# NusbioV2_Board.net
KiCad netlist of a schematic drawn in EAGLE
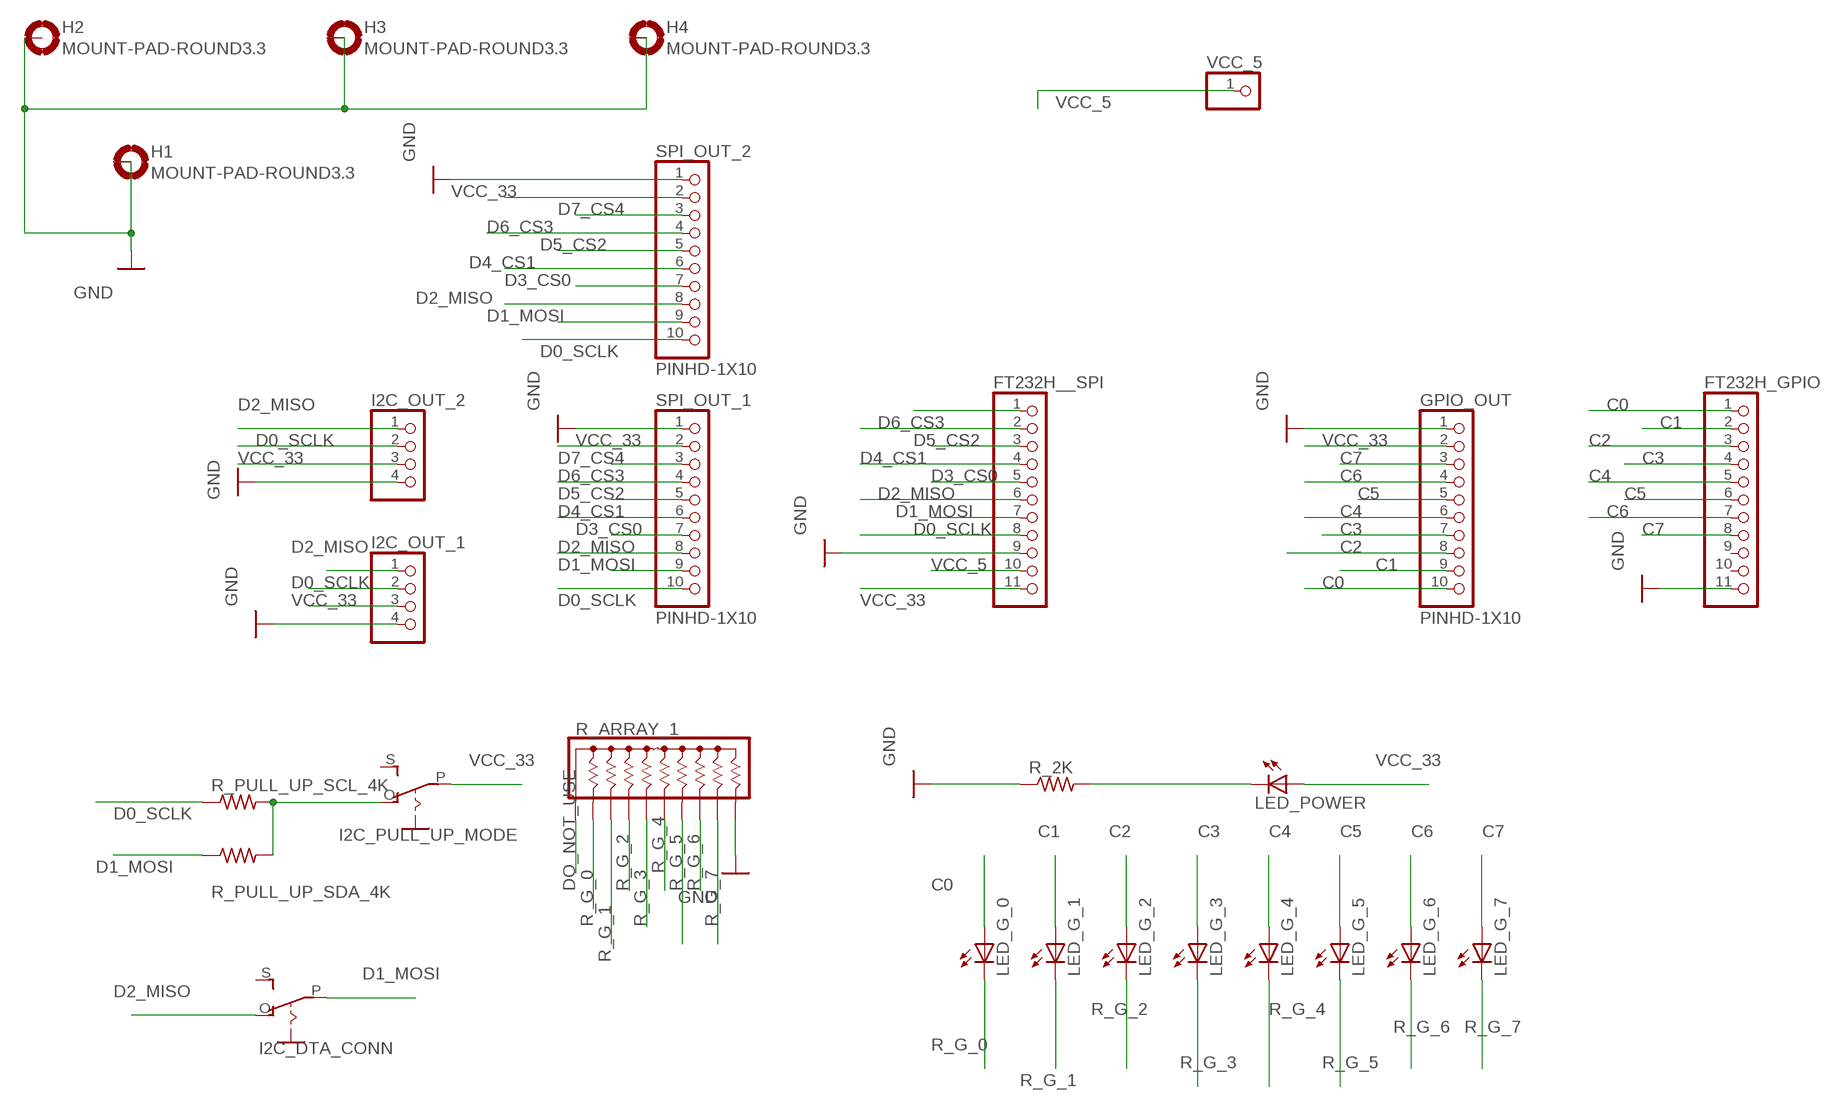
[diagram p0: schematic, sheet 1]

(export (version "E")
  (design (tool "Eeschema 10.0.6"))
  (components
    (comp (ref "FT232H_GPIO")
      (value "PINHD-1X11")
      (footprint "eagle-import:1X11")
      (libsource (lib "eagle-import") (part "PINHD-1X11"))
    )
    (comp (ref "FT232H__SPI")
      (value "PINHD-1X11")
      (footprint "eagle-import:1X11")
      (libsource (lib "eagle-import") (part "PINHD-1X11"))
    )
    (comp (ref "GPIO_OUT")
      (value "PINHD-1X10")
      (footprint "eagle-import:1X10-BIG")
      (libsource (lib "eagle-import") (part "PINHD-1X10"))
    )
    (comp (ref "H1")
      (value "MOUNT-PAD-ROUND3.3")
      (footprint "eagle-import:3,3-PAD")
      (libsource (lib "eagle-import") (part "MOUNT-PAD-ROUND3.3"))
    )
    (comp (ref "H2")
      (value "MOUNT-PAD-ROUND3.3")
      (footprint "eagle-import:3,3-PAD")
      (libsource (lib "eagle-import") (part "MOUNT-PAD-ROUND3.3"))
    )
    (comp (ref "H3")
      (value "MOUNT-PAD-ROUND3.3")
      (footprint "eagle-import:3,3-PAD")
      (libsource (lib "eagle-import") (part "MOUNT-PAD-ROUND3.3"))
    )
    (comp (ref "H4")
      (value "MOUNT-PAD-ROUND3.3")
      (footprint "eagle-import:3,3-PAD")
      (libsource (lib "eagle-import") (part "MOUNT-PAD-ROUND3.3"))
    )
    (comp (ref "I2C_DTA_CONN")
      (value "EG1218S")
      (footprint "eagle-import:EG1218")
      (libsource (lib "eagle-import") (part "EG1218S"))
    )
    (comp (ref "I2C_OUT_1")
      (value "PINHD-1X4")
      (footprint "eagle-import:1X04")
      (libsource (lib "eagle-import") (part "PINHD-1X4"))
    )
    (comp (ref "I2C_OUT_2")
      (value "PINHD-1X4")
      (footprint "eagle-import:1X04")
      (libsource (lib "eagle-import") (part "PINHD-1X4"))
    )
    (comp (ref "I2C_PULL_UP_MODE")
      (value "EG1218S")
      (footprint "eagle-import:EG1218")
      (libsource (lib "eagle-import") (part "EG1218S"))
    )
    (comp (ref "LED_G_0")
      (value "LEDSMT1206")
      (footprint "eagle-import:1206")
      (libsource (lib "eagle-import") (part "LEDSMT1206"))
    )
    (comp (ref "LED_G_1")
      (value "LEDSMT1206")
      (footprint "eagle-import:1206")
      (libsource (lib "eagle-import") (part "LEDSMT1206"))
    )
    (comp (ref "LED_G_2")
      (value "LEDSMT1206")
      (footprint "eagle-import:1206")
      (libsource (lib "eagle-import") (part "LEDSMT1206"))
    )
    (comp (ref "LED_G_3")
      (value "LEDSMT1206")
      (footprint "eagle-import:1206")
      (libsource (lib "eagle-import") (part "LEDSMT1206"))
    )
    (comp (ref "LED_G_4")
      (value "LEDSMT1206")
      (footprint "eagle-import:1206")
      (libsource (lib "eagle-import") (part "LEDSMT1206"))
    )
    (comp (ref "LED_G_5")
      (value "LEDSMT1206")
      (footprint "eagle-import:1206")
      (libsource (lib "eagle-import") (part "LEDSMT1206"))
    )
    (comp (ref "LED_G_6")
      (value "LEDSMT1206")
      (footprint "eagle-import:1206")
      (libsource (lib "eagle-import") (part "LEDSMT1206"))
    )
    (comp (ref "LED_G_7")
      (value "LEDSMT1206")
      (footprint "eagle-import:1206")
      (libsource (lib "eagle-import") (part "LEDSMT1206"))
    )
    (comp (ref "LED_POWER")
      (value "LEDSMT1206")
      (footprint "eagle-import:1206")
      (libsource (lib "eagle-import") (part "LEDSMT1206"))
    )
    (comp (ref "R_2K")
      (value "R-US_R1206")
      (footprint "eagle-import:R1206")
      (libsource (lib "eagle-import") (part "R-US_R1206"))
    )
    (comp (ref "R_ARRAY_1")
      (value "4610X")
      (footprint "eagle-import:SIP10")
      (libsource (lib "eagle-import") (part "4610X"))
    )
    (comp (ref "R_PULL_UP_SCL_4K")
      (value "R-US_R1206")
      (footprint "eagle-import:R1206")
      (libsource (lib "eagle-import") (part "R-US_R1206"))
    )
    (comp (ref "R_PULL_UP_SDA_4K")
      (value "R-US_R1206")
      (footprint "eagle-import:R1206")
      (libsource (lib "eagle-import") (part "R-US_R1206"))
    )
    (comp (ref "SPI_OUT_1")
      (value "PINHD-1X10")
      (footprint "eagle-import:1X10-BIG")
      (libsource (lib "eagle-import") (part "PINHD-1X10"))
    )
    (comp (ref "SPI_OUT_2")
      (value "PINHD-1X10")
      (footprint "eagle-import:1X10-BIG")
      (libsource (lib "eagle-import") (part "PINHD-1X10"))
    )
    (comp (ref "VCC_5")
      (value "PINHD-1X1")
      (footprint "eagle-import:1X01")
      (libsource (lib "eagle-import") (part "PINHD-1X1"))
    )
  )
  (nets
    (net (code "1") (name "/C0") (class "Default")
      (node (ref "FT232H_GPIO") (pin "1") (pinfunction "1_1") (pintype "passive"))
      (node (ref "GPIO_OUT") (pin "10") (pinfunction "10_10") (pintype "passive"))
      (node (ref "LED_G_0") (pin "A") (pinfunction "A_A") (pintype "passive"))
    )
    (net (code "2") (name "/C1") (class "Default")
      (node (ref "FT232H_GPIO") (pin "2") (pinfunction "2_2") (pintype "passive"))
      (node (ref "GPIO_OUT") (pin "9") (pinfunction "9_9") (pintype "passive"))
      (node (ref "LED_G_1") (pin "A") (pinfunction "A_A") (pintype "passive"))
    )
    (net (code "3") (name "/C2") (class "Default")
      (node (ref "FT232H_GPIO") (pin "3") (pinfunction "3_3") (pintype "passive"))
      (node (ref "GPIO_OUT") (pin "8") (pinfunction "8_8") (pintype "passive"))
      (node (ref "LED_G_2") (pin "A") (pinfunction "A_A") (pintype "passive"))
    )
    (net (code "4") (name "/C3") (class "Default")
      (node (ref "FT232H_GPIO") (pin "4") (pinfunction "4_4") (pintype "passive"))
      (node (ref "GPIO_OUT") (pin "7") (pinfunction "7_7") (pintype "passive"))
      (node (ref "LED_G_3") (pin "A") (pinfunction "A_A") (pintype "passive"))
    )
    (net (code "5") (name "/C4") (class "Default")
      (node (ref "FT232H_GPIO") (pin "5") (pinfunction "5_5") (pintype "passive"))
      (node (ref "GPIO_OUT") (pin "6") (pinfunction "6_6") (pintype "passive"))
      (node (ref "LED_G_4") (pin "A") (pinfunction "A_A") (pintype "passive"))
    )
    (net (code "6") (name "/C5") (class "Default")
      (node (ref "FT232H_GPIO") (pin "6") (pinfunction "6_6") (pintype "passive"))
      (node (ref "GPIO_OUT") (pin "5") (pinfunction "5_5") (pintype "passive"))
      (node (ref "LED_G_5") (pin "A") (pinfunction "A_A") (pintype "passive"))
    )
    (net (code "7") (name "/C6") (class "Default")
      (node (ref "FT232H_GPIO") (pin "7") (pinfunction "7_7") (pintype "passive"))
      (node (ref "GPIO_OUT") (pin "4") (pinfunction "4_4") (pintype "passive"))
      (node (ref "LED_G_6") (pin "A") (pinfunction "A_A") (pintype "passive"))
    )
    (net (code "8") (name "/C7") (class "Default")
      (node (ref "FT232H_GPIO") (pin "8") (pinfunction "8_8") (pintype "passive"))
      (node (ref "GPIO_OUT") (pin "3") (pinfunction "3_3") (pintype "passive"))
      (node (ref "LED_G_7") (pin "A") (pinfunction "A_A") (pintype "passive"))
    )
    (net (code "9") (name "/D0_SCLK") (class "Default")
      (node (ref "FT232H__SPI") (pin "8") (pinfunction "8_8") (pintype "passive"))
      (node (ref "I2C_OUT_1") (pin "2") (pinfunction "2_2") (pintype "passive"))
      (node (ref "I2C_OUT_2") (pin "2") (pinfunction "2_2") (pintype "passive"))
      (node (ref "R_PULL_UP_SCL_4K") (pin "1") (pinfunction "1_1") (pintype "passive"))
      (node (ref "SPI_OUT_1") (pin "10") (pinfunction "10_10") (pintype "passive"))
      (node (ref "SPI_OUT_2") (pin "10") (pinfunction "10_10") (pintype "passive"))
    )
    (net (code "10") (name "/D1_MOSI") (class "Default")
      (node (ref "FT232H__SPI") (pin "7") (pinfunction "7_7") (pintype "passive"))
      (node (ref "I2C_DTA_CONN") (pin "P") (pinfunction "P_P") (pintype "passive"))
      (node (ref "R_PULL_UP_SDA_4K") (pin "1") (pinfunction "1_1") (pintype "passive"))
      (node (ref "SPI_OUT_1") (pin "9") (pinfunction "9_9") (pintype "passive"))
      (node (ref "SPI_OUT_2") (pin "9") (pinfunction "9_9") (pintype "passive"))
    )
    (net (code "11") (name "/D2_MISO") (class "Default")
      (node (ref "FT232H__SPI") (pin "6") (pinfunction "6_6") (pintype "passive"))
      (node (ref "I2C_DTA_CONN") (pin "O") (pinfunction "O_O") (pintype "passive"))
      (node (ref "I2C_OUT_1") (pin "1") (pinfunction "1_1") (pintype "passive"))
      (node (ref "I2C_OUT_2") (pin "1") (pinfunction "1_1") (pintype "passive"))
      (node (ref "SPI_OUT_1") (pin "8") (pinfunction "8_8") (pintype "passive"))
      (node (ref "SPI_OUT_2") (pin "8") (pinfunction "8_8") (pintype "passive"))
    )
    (net (code "12") (name "/D3_CS0") (class "Default")
      (node (ref "FT232H__SPI") (pin "5") (pinfunction "5_5") (pintype "passive"))
      (node (ref "SPI_OUT_1") (pin "7") (pinfunction "7_7") (pintype "passive"))
      (node (ref "SPI_OUT_2") (pin "7") (pinfunction "7_7") (pintype "passive"))
    )
    (net (code "13") (name "/D4_CS1") (class "Default")
      (node (ref "FT232H__SPI") (pin "4") (pinfunction "4_4") (pintype "passive"))
      (node (ref "SPI_OUT_1") (pin "6") (pinfunction "6_6") (pintype "passive"))
      (node (ref "SPI_OUT_2") (pin "6") (pinfunction "6_6") (pintype "passive"))
    )
    (net (code "14") (name "/D5_CS2") (class "Default")
      (node (ref "FT232H__SPI") (pin "3") (pinfunction "3_3") (pintype "passive"))
      (node (ref "SPI_OUT_1") (pin "5") (pinfunction "5_5") (pintype "passive"))
      (node (ref "SPI_OUT_2") (pin "5") (pinfunction "5_5") (pintype "passive"))
    )
    (net (code "15") (name "/D6_CS3") (class "Default")
      (node (ref "FT232H__SPI") (pin "2") (pinfunction "2_2") (pintype "passive"))
      (node (ref "SPI_OUT_1") (pin "4") (pinfunction "4_4") (pintype "passive"))
      (node (ref "SPI_OUT_2") (pin "4") (pinfunction "4_4") (pintype "passive"))
    )
    (net (code "16") (name "/D7_CS4") (class "Default")
      (node (ref "FT232H__SPI") (pin "1") (pinfunction "1_1") (pintype "passive"))
      (node (ref "SPI_OUT_1") (pin "3") (pinfunction "3_3") (pintype "passive"))
      (node (ref "SPI_OUT_2") (pin "3") (pinfunction "3_3") (pintype "passive"))
    )
    (net (code "17") (name "/DO_NOT_USE") (class "Default")
      (node (ref "R_ARRAY_1") (pin "1") (pinfunction "1_1") (pintype "passive"))
    )
    (net (code "18") (name "/R_G_0") (class "Default")
      (node (ref "LED_G_0") (pin "C") (pinfunction "C_C") (pintype "passive"))
      (node (ref "R_ARRAY_1") (pin "2") (pinfunction "2_2") (pintype "passive"))
    )
    (net (code "19") (name "/R_G_1") (class "Default")
      (node (ref "LED_G_1") (pin "C") (pinfunction "C_C") (pintype "passive"))
      (node (ref "R_ARRAY_1") (pin "3") (pinfunction "3_3") (pintype "passive"))
    )
    (net (code "20") (name "/R_G_2") (class "Default")
      (node (ref "LED_G_2") (pin "C") (pinfunction "C_C") (pintype "passive"))
      (node (ref "R_ARRAY_1") (pin "4") (pinfunction "4_4") (pintype "passive"))
    )
    (net (code "21") (name "/R_G_3") (class "Default")
      (node (ref "LED_G_3") (pin "C") (pinfunction "C_C") (pintype "passive"))
      (node (ref "R_ARRAY_1") (pin "5") (pinfunction "5_5") (pintype "passive"))
    )
    (net (code "22") (name "/R_G_4") (class "Default")
      (node (ref "LED_G_4") (pin "C") (pinfunction "C_C") (pintype "passive"))
      (node (ref "R_ARRAY_1") (pin "6") (pinfunction "6_6") (pintype "passive"))
    )
    (net (code "23") (name "/R_G_5") (class "Default")
      (node (ref "LED_G_5") (pin "C") (pinfunction "C_C") (pintype "passive"))
      (node (ref "R_ARRAY_1") (pin "7") (pinfunction "7_7") (pintype "passive"))
    )
    (net (code "24") (name "/R_G_6") (class "Default")
      (node (ref "LED_G_6") (pin "C") (pinfunction "C_C") (pintype "passive"))
      (node (ref "R_ARRAY_1") (pin "8") (pinfunction "8_8") (pintype "passive"))
    )
    (net (code "25") (name "/R_G_7") (class "Default")
      (node (ref "LED_G_7") (pin "C") (pinfunction "C_C") (pintype "passive"))
      (node (ref "R_ARRAY_1") (pin "9") (pinfunction "9_9") (pintype "passive"))
    )
    (net (code "26") (name "/VCC_5") (class "Default")
      (node (ref "FT232H__SPI") (pin "10") (pinfunction "10_10") (pintype "passive"))
      (node (ref "VCC_5") (pin "1") (pinfunction "1_1") (pintype "passive"))
    )
    (net (code "27") (name "/VCC_33") (class "Default")
      (node (ref "FT232H__SPI") (pin "11") (pinfunction "11_11") (pintype "passive"))
      (node (ref "GPIO_OUT") (pin "2") (pinfunction "2_2") (pintype "passive"))
      (node (ref "I2C_OUT_1") (pin "3") (pinfunction "3_3") (pintype "passive"))
      (node (ref "I2C_OUT_2") (pin "3") (pinfunction "3_3") (pintype "passive"))
      (node (ref "I2C_PULL_UP_MODE") (pin "P") (pinfunction "P_P") (pintype "passive"))
      (node (ref "LED_POWER") (pin "A") (pinfunction "A_A") (pintype "passive"))
      (node (ref "SPI_OUT_1") (pin "2") (pinfunction "2_2") (pintype "passive"))
      (node (ref "SPI_OUT_2") (pin "2") (pinfunction "2_2") (pintype "passive"))
    )
    (net (code "28") (name "GND") (class "Default")
      (node (ref "FT232H_GPIO") (pin "11") (pinfunction "11_11") (pintype "passive"))
      (node (ref "FT232H__SPI") (pin "9") (pinfunction "9_9") (pintype "passive"))
      (node (ref "GPIO_OUT") (pin "1") (pinfunction "1_1") (pintype "passive"))
      (node (ref "H1") (pin "B3,3") (pinfunction "MOUNT_B3,3") (pintype "passive"))
      (node (ref "H2") (pin "B3,3") (pinfunction "MOUNT_B3,3") (pintype "passive"))
      (node (ref "H3") (pin "B3,3") (pinfunction "MOUNT_B3,3") (pintype "passive"))
      (node (ref "H4") (pin "B3,3") (pinfunction "MOUNT_B3,3") (pintype "passive"))
      (node (ref "I2C_OUT_1") (pin "4") (pinfunction "4_4") (pintype "passive"))
      (node (ref "I2C_OUT_2") (pin "4") (pinfunction "4_4") (pintype "passive"))
      (node (ref "R_2K") (pin "1") (pinfunction "1_1") (pintype "passive"))
      (node (ref "R_ARRAY_1") (pin "10") (pinfunction "10_10") (pintype "passive"))
      (node (ref "SPI_OUT_1") (pin "1") (pinfunction "1_1") (pintype "passive"))
      (node (ref "SPI_OUT_2") (pin "1") (pinfunction "1_1") (pintype "passive"))
    )
    (net (code "29") (name "Net-(I2C_PULL_UP_MODE-PadO)") (class "Default")
      (node (ref "I2C_PULL_UP_MODE") (pin "O") (pinfunction "O_O") (pintype "passive"))
      (node (ref "R_PULL_UP_SCL_4K") (pin "2") (pinfunction "2_2") (pintype "passive"))
      (node (ref "R_PULL_UP_SDA_4K") (pin "2") (pinfunction "2_2") (pintype "passive"))
    )
    (net (code "30") (name "Net-(LED_POWER-PadC)") (class "Default")
      (node (ref "LED_POWER") (pin "C") (pinfunction "C_C") (pintype "passive"))
      (node (ref "R_2K") (pin "2") (pinfunction "2_2") (pintype "passive"))
    )
    (net (code "31") (name "unconnected-(FT232H_GPIO-Pad9)") (class "Default")
      (node (ref "FT232H_GPIO") (pin "9") (pinfunction "9_9") (pintype "passive"))
    )
    (net (code "32") (name "unconnected-(FT232H_GPIO-Pad10)") (class "Default")
      (node (ref "FT232H_GPIO") (pin "10") (pinfunction "10_10") (pintype "passive"))
    )
    (net (code "33") (name "unconnected-(I2C_DTA_CONN-PadS)") (class "Default")
      (node (ref "I2C_DTA_CONN") (pin "S") (pinfunction "S_S") (pintype "passive"))
    )
    (net (code "34") (name "unconnected-(I2C_PULL_UP_MODE-PadS)") (class "Default")
      (node (ref "I2C_PULL_UP_MODE") (pin "S") (pinfunction "S_S") (pintype "passive"))
    )
  )
)
